# LED.net
KiCad netlist of a schematic drawn in Altium Designer
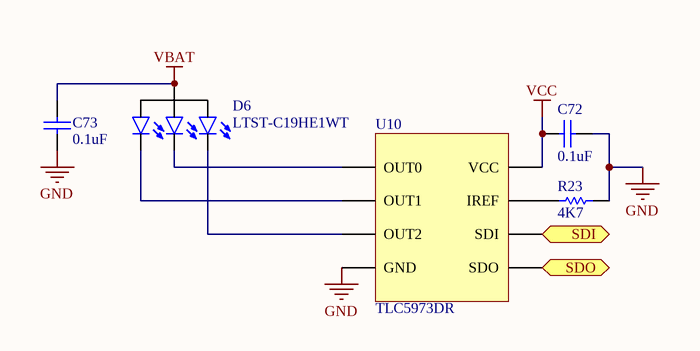
[diagram p0: LED.SchDoc]

(export (version "E")
  (design (tool "Eeschema 10.0.6"))
  (components
    (comp (ref "C72")
      (value "0.1uF")
      (footprint "C0402[1005X55]")
      (description "0.1uF 6.3V 10% 0402 (1005 Metric)")
      (fields (field (name "PARTNUMBER") "GRM155R70J104KA01D") (field (name "MANUFACTURER") "Murata"))
      (libsource (lib "Capacitors") (part "CAP_0.1uF_6.3V_0402_10%"))
    )
    (comp (ref "C73")
      (value "0.1uF")
      (footprint "C0402[1005X55]")
      (description "0.1uF 6.3V 10% 0402 (1005 Metric)")
      (fields (field (name "PARTNUMBER") "GRM155R70J104KA01D") (field (name "MANUFACTURER") "Murata"))
      (libsource (lib "Capacitors") (part "CAP_0.1uF_6.3V_0402_10%"))
    )
    (comp (ref "D6")
      (value "LTST-C19HE1WT")
      (footprint "LED0606")
      (fields (field (name "MANUFACTURER") "Lite-On Inc."))
      (libsource (lib "LEDs") (part "LTST-C19HE1WT"))
    )
    (comp (ref "R23")
      (value "4K7")
      (footprint "R0402[1005]")
      (description "4K7 0.063W 1% 0402 (1005 Metric)")
      (fields (field (name "MANUFACTURER") "KOA Speer") (field (name "PARTNUMBER") "RK73H1ETTP4701F"))
      (libsource (lib "Resistors") (part "RES_4K7_0402_1%"))
    )
    (comp (ref "U10")
      (value "TLC5973DR")
      (footprint "SOIC-8")
      (description "LED Lighting Drivers 3Ch 12B PWM Constant Crnt LED Dvr")
      (fields (field (name "MANUFACTURER") "Texas Instruments"))
      (libsource (lib "ICs") (part "TLC5973DR"))
    )
  )
  (nets
    (net (code "1") (name "/SDI") (class "Default")
      (node (ref "U10") (pin "6") (pinfunction "SDI_6") (pintype "passive"))
    )
    (net (code "2") (name "/SDO") (class "Default")
      (node (ref "U10") (pin "5") (pinfunction "SDO_5") (pintype "passive"))
    )
    (net (code "3") (name "GND") (class "Default")
      (node (ref "C72") (pin "2") (pinfunction "2_2") (pintype "passive"))
      (node (ref "C73") (pin "1") (pinfunction "1_1") (pintype "passive"))
      (node (ref "R23") (pin "1") (pinfunction "1_1") (pintype "passive"))
      (node (ref "U10") (pin "4") (pinfunction "GND_4") (pintype "power_in"))
    )
    (net (code "4") (name "Net-(D6-K_Blue)") (class "Default")
      (node (ref "D6") (pin "3") (pinfunction "K_Blue_3") (pintype "passive"))
      (node (ref "U10") (pin "2") (pinfunction "OUT1_2") (pintype "passive"))
    )
    (net (code "5") (name "Net-(D6-K_Green)") (class "Default")
      (node (ref "D6") (pin "2") (pinfunction "K_Green_2") (pintype "passive"))
      (node (ref "U10") (pin "1") (pinfunction "OUT0_1") (pintype "passive"))
    )
    (net (code "6") (name "Net-(D6-K_Red)") (class "Default")
      (node (ref "D6") (pin "1") (pinfunction "K_Red_1") (pintype "passive"))
      (node (ref "U10") (pin "3") (pinfunction "OUT2_3") (pintype "passive"))
    )
    (net (code "7") (name "Net-(U10-IREF)") (class "Default")
      (node (ref "R23") (pin "2") (pinfunction "2_2") (pintype "passive"))
      (node (ref "U10") (pin "7") (pinfunction "IREF_7") (pintype "passive"))
    )
    (net (code "8") (name "VBAT") (class "Default")
      (node (ref "C73") (pin "2") (pinfunction "2_2") (pintype "passive"))
      (node (ref "D6") (pin "4") (pinfunction "A_4") (pintype "passive"))
    )
    (net (code "9") (name "VCC") (class "Default")
      (node (ref "C72") (pin "1") (pinfunction "1_1") (pintype "passive"))
      (node (ref "U10") (pin "8") (pinfunction "VCC_8") (pintype "power_in"))
    )
  )
)
